# interface2.net
KiCad netlist of a schematic drawn in EAGLE
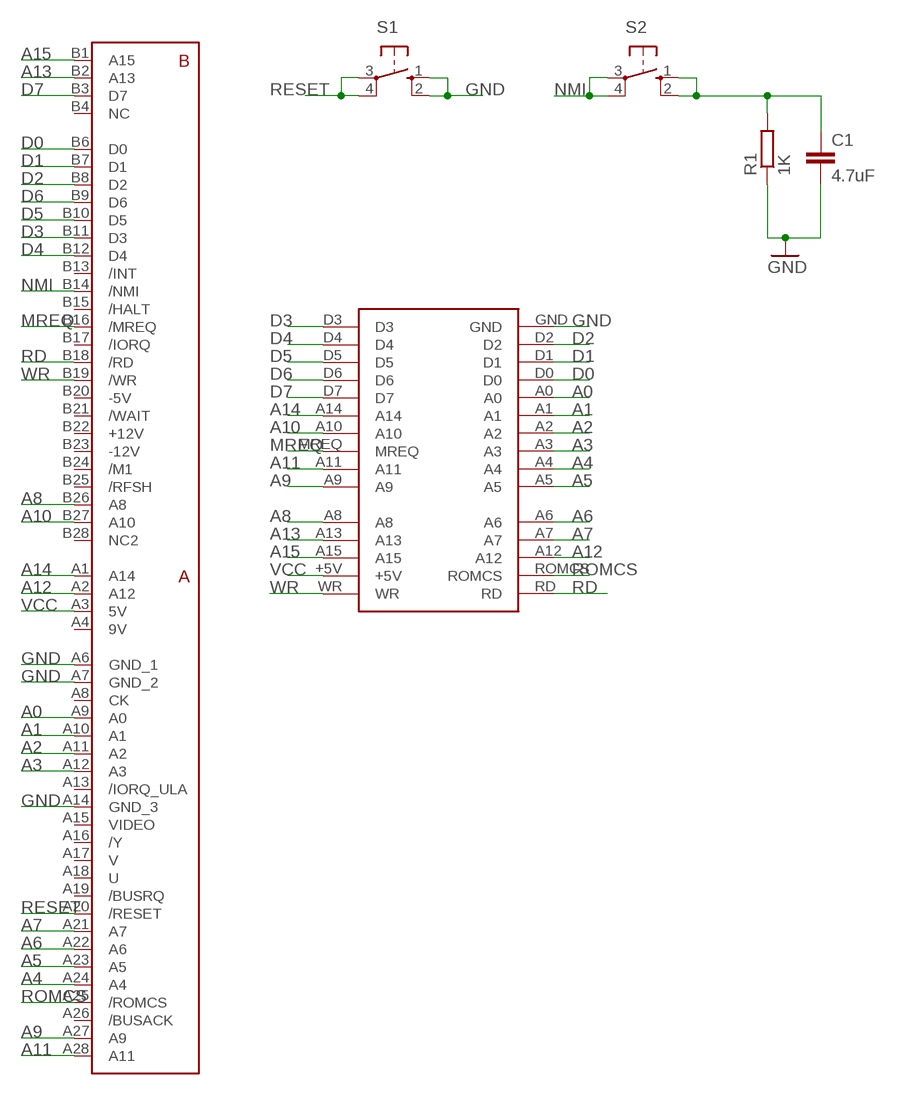
[diagram p0: schematic, sheet 1]

(export (version "E")
  (design (tool "Eeschema 10.0.6"))
  (components
    (comp (ref "C1")
      (value "4.7uF")
      (footprint "eagle-import:C025-025X050")
      (libsource (lib "eagle-import") (part "C-EU025-025X050"))
    )
    (comp (ref "R1")
      (value "1K")
      (footprint "eagle-import:0204_5")
      (libsource (lib "eagle-import") (part "R-EU_0204/5"))
    )
    (comp (ref "S1")
      (value "10-XX")
      (footprint "eagle-import:B3F-10XX")
      (fields (field (name "MPN") "B3F-1000"))
      (libsource (lib "eagle-import") (part "10-XX"))
    )
    (comp (ref "S2")
      (value "10-XX")
      (footprint "eagle-import:B3F-10XX")
      (fields (field (name "MPN") "B3F-1000"))
      (libsource (lib "eagle-import") (part "10-XX"))
    )
    (comp (ref "U$1")
      (value "ZX_CARTRIDGE")
      (footprint "eagle-import:ZX_CARTRIDGE")
      (libsource (lib "eagle-import") (part "ZX_CARTRIDGE"))
    )
    (comp (ref "U$3")
      (value "ZXSP_ED2X28_SPE")
      (footprint "eagle-import:2X28_SPE")
      (libsource (lib "eagle-import") (part "ZXSP_ED2X28_SPE"))
    )
  )
  (nets
    (net (code "1") (name "/+12V") (class "Default")
      (node (ref "U$3") (pin "B22") (pinfunction "+12V_B22") (pintype "power_in"))
    )
    (net (code "2") (name "/-5V") (class "Default")
      (node (ref "U$3") (pin "B20") (pinfunction "-5V_B20") (pintype "power_in"))
    )
    (net (code "3") (name "/-12V") (class "Default")
      (node (ref "U$3") (pin "B23") (pinfunction "-12V_B23") (pintype "power_in"))
    )
    (net (code "4") (name "/9V") (class "Default")
      (node (ref "U$3") (pin "A4") (pinfunction "9V_A4") (pintype "power_in"))
    )
    (net (code "5") (name "/A0") (class "Default")
      (node (ref "U$1") (pin "A0") (pinfunction "A0_A0") (pintype "bidirectional"))
      (node (ref "U$3") (pin "A9") (pinfunction "A0_A9") (pintype "bidirectional"))
    )
    (net (code "6") (name "/A1") (class "Default")
      (node (ref "U$1") (pin "A1") (pinfunction "A1_A1") (pintype "bidirectional"))
      (node (ref "U$3") (pin "A10") (pinfunction "A1_A10") (pintype "bidirectional"))
    )
    (net (code "7") (name "/A2") (class "Default")
      (node (ref "U$1") (pin "A2") (pinfunction "A2_A2") (pintype "bidirectional"))
      (node (ref "U$3") (pin "A11") (pinfunction "A2_A11") (pintype "bidirectional"))
    )
    (net (code "8") (name "/A3") (class "Default")
      (node (ref "U$1") (pin "A3") (pinfunction "A3_A3") (pintype "bidirectional"))
      (node (ref "U$3") (pin "A12") (pinfunction "A3_A12") (pintype "bidirectional"))
    )
    (net (code "9") (name "/A4") (class "Default")
      (node (ref "U$1") (pin "A4") (pinfunction "A4_A4") (pintype "bidirectional"))
      (node (ref "U$3") (pin "A24") (pinfunction "A4_A24") (pintype "bidirectional"))
    )
    (net (code "10") (name "/A5") (class "Default")
      (node (ref "U$1") (pin "A5") (pinfunction "A5_A5") (pintype "bidirectional"))
      (node (ref "U$3") (pin "A23") (pinfunction "A5_A23") (pintype "bidirectional"))
    )
    (net (code "11") (name "/A6") (class "Default")
      (node (ref "U$1") (pin "A6") (pinfunction "A6_A6") (pintype "bidirectional"))
      (node (ref "U$3") (pin "A22") (pinfunction "A6_A22") (pintype "bidirectional"))
    )
    (net (code "12") (name "/A7") (class "Default")
      (node (ref "U$1") (pin "A7") (pinfunction "A7_A7") (pintype "bidirectional"))
      (node (ref "U$3") (pin "A21") (pinfunction "A7_A21") (pintype "bidirectional"))
    )
    (net (code "13") (name "/A8") (class "Default")
      (node (ref "U$1") (pin "A8") (pinfunction "A8_A8") (pintype "bidirectional"))
      (node (ref "U$3") (pin "B26") (pinfunction "A8_B26") (pintype "bidirectional"))
    )
    (net (code "14") (name "/A9") (class "Default")
      (node (ref "U$1") (pin "A9") (pinfunction "A9_A9") (pintype "bidirectional"))
      (node (ref "U$3") (pin "A27") (pinfunction "A9_A27") (pintype "bidirectional"))
    )
    (net (code "15") (name "/A10") (class "Default")
      (node (ref "U$1") (pin "A10") (pinfunction "A10_A10") (pintype "bidirectional"))
      (node (ref "U$3") (pin "B27") (pinfunction "A10_B27") (pintype "bidirectional"))
    )
    (net (code "16") (name "/A11") (class "Default")
      (node (ref "U$1") (pin "A11") (pinfunction "A11_A11") (pintype "bidirectional"))
      (node (ref "U$3") (pin "A28") (pinfunction "A11_A28") (pintype "bidirectional"))
    )
    (net (code "17") (name "/A12") (class "Default")
      (node (ref "U$1") (pin "A12") (pinfunction "A12_A12") (pintype "bidirectional"))
      (node (ref "U$3") (pin "A2") (pinfunction "A12_A2") (pintype "bidirectional"))
    )
    (net (code "18") (name "/A13") (class "Default")
      (node (ref "U$1") (pin "A13") (pinfunction "A13_A13") (pintype "bidirectional"))
      (node (ref "U$3") (pin "B2") (pinfunction "A13_B2") (pintype "bidirectional"))
    )
    (net (code "19") (name "/A14") (class "Default")
      (node (ref "U$1") (pin "A14") (pinfunction "A14_A14") (pintype "bidirectional"))
      (node (ref "U$3") (pin "A1") (pinfunction "A14_A1") (pintype "bidirectional"))
    )
    (net (code "20") (name "/A15") (class "Default")
      (node (ref "U$1") (pin "A15") (pinfunction "A15_A15") (pintype "bidirectional"))
      (node (ref "U$3") (pin "B1") (pinfunction "A15_B1") (pintype "bidirectional"))
    )
    (net (code "21") (name "/D0") (class "Default")
      (node (ref "U$1") (pin "D0") (pinfunction "D0_D0") (pintype "bidirectional"))
      (node (ref "U$3") (pin "B6") (pinfunction "D0_B6") (pintype "bidirectional"))
    )
    (net (code "22") (name "/D1") (class "Default")
      (node (ref "U$1") (pin "D1") (pinfunction "D1_D1") (pintype "bidirectional"))
      (node (ref "U$3") (pin "B7") (pinfunction "D1_B7") (pintype "bidirectional"))
    )
    (net (code "23") (name "/D2") (class "Default")
      (node (ref "U$1") (pin "D2") (pinfunction "D2_D2") (pintype "bidirectional"))
      (node (ref "U$3") (pin "B8") (pinfunction "D2_B8") (pintype "bidirectional"))
    )
    (net (code "24") (name "/D3") (class "Default")
      (node (ref "U$1") (pin "D3") (pinfunction "D3_D3") (pintype "bidirectional"))
      (node (ref "U$3") (pin "B11") (pinfunction "D3_B11") (pintype "bidirectional"))
    )
    (net (code "25") (name "/D4") (class "Default")
      (node (ref "U$1") (pin "D4") (pinfunction "D4_D4") (pintype "bidirectional"))
      (node (ref "U$3") (pin "B12") (pinfunction "D4_B12") (pintype "bidirectional"))
    )
    (net (code "26") (name "/D5") (class "Default")
      (node (ref "U$1") (pin "D5") (pinfunction "D5_D5") (pintype "bidirectional"))
      (node (ref "U$3") (pin "B10") (pinfunction "D5_B10") (pintype "bidirectional"))
    )
    (net (code "27") (name "/D6") (class "Default")
      (node (ref "U$1") (pin "D6") (pinfunction "D6_D6") (pintype "bidirectional"))
      (node (ref "U$3") (pin "B9") (pinfunction "D6_B9") (pintype "bidirectional"))
    )
    (net (code "28") (name "/D7") (class "Default")
      (node (ref "U$1") (pin "D7") (pinfunction "D7_D7") (pintype "bidirectional"))
      (node (ref "U$3") (pin "B3") (pinfunction "D7_B3") (pintype "bidirectional"))
    )
    (net (code "29") (name "/MREQ") (class "Default")
      (node (ref "U$1") (pin "MREQ") (pinfunction "MREQ_MREQ") (pintype "bidirectional"))
      (node (ref "U$3") (pin "B16") (pinfunction "/MREQ_B16") (pintype "bidirectional"))
    )
    (net (code "30") (name "/NMI") (class "Default")
      (node (ref "S2") (pin "3") (pinfunction "P_3") (pintype "passive"))
      (node (ref "S2") (pin "4") (pinfunction "P1_4") (pintype "passive"))
      (node (ref "U$3") (pin "B14") (pinfunction "/NMI_B14") (pintype "bidirectional"))
    )
    (net (code "31") (name "/RD") (class "Default")
      (node (ref "U$1") (pin "RD") (pinfunction "RD_RD") (pintype "bidirectional"))
      (node (ref "U$3") (pin "B18") (pinfunction "/RD_B18") (pintype "bidirectional"))
    )
    (net (code "32") (name "/RESET") (class "Default")
      (node (ref "S1") (pin "3") (pinfunction "P_3") (pintype "passive"))
      (node (ref "S1") (pin "4") (pinfunction "P1_4") (pintype "passive"))
      (node (ref "U$3") (pin "A20") (pinfunction "/RESET_A20") (pintype "bidirectional"))
    )
    (net (code "33") (name "/ROMCS") (class "Default")
      (node (ref "U$1") (pin "ROMCS") (pinfunction "ROMCS_ROMCS") (pintype "bidirectional"))
      (node (ref "U$3") (pin "A25") (pinfunction "/ROMCS_A25") (pintype "bidirectional"))
    )
    (net (code "34") (name "/VCC") (class "Default")
      (node (ref "U$1") (pin "+5V") (pinfunction "+5V_+5V") (pintype "bidirectional"))
      (node (ref "U$3") (pin "A3") (pinfunction "5V_A3") (pintype "power_in"))
    )
    (net (code "35") (name "/WR") (class "Default")
      (node (ref "U$1") (pin "WR") (pinfunction "WR_WR") (pintype "bidirectional"))
      (node (ref "U$3") (pin "B19") (pinfunction "/WR_B19") (pintype "bidirectional"))
    )
    (net (code "36") (name "GND") (class "Default")
      (node (ref "C1") (pin "2") (pinfunction "2_2") (pintype "passive"))
      (node (ref "R1") (pin "1") (pinfunction "1_1") (pintype "passive"))
      (node (ref "S1") (pin "1") (pinfunction "S_1") (pintype "passive"))
      (node (ref "S1") (pin "2") (pinfunction "S1_2") (pintype "passive"))
      (node (ref "U$1") (pin "GND") (pinfunction "GND_GND") (pintype "bidirectional"))
      (node (ref "U$3") (pin "A14") (pinfunction "GND_3_A14") (pintype "power_in"))
      (node (ref "U$3") (pin "A6") (pinfunction "GND_1_A6") (pintype "power_in"))
      (node (ref "U$3") (pin "A7") (pinfunction "GND_2_A7") (pintype "power_in"))
    )
    (net (code "37") (name "Net-(S2-S)") (class "Default")
      (node (ref "C1") (pin "1") (pinfunction "1_1") (pintype "passive"))
      (node (ref "R1") (pin "2") (pinfunction "2_2") (pintype "passive"))
      (node (ref "S2") (pin "1") (pinfunction "S_1") (pintype "passive"))
      (node (ref "S2") (pin "2") (pinfunction "S1_2") (pintype "passive"))
    )
    (net (code "38") (name "unconnected-(U$3-CK-PadA8)") (class "Default")
      (node (ref "U$3") (pin "A8") (pinfunction "CK_A8") (pintype "bidirectional"))
    )
    (net (code "39") (name "unconnected-(U$3-NC-PadB4)") (class "Default")
      (node (ref "U$3") (pin "B4") (pinfunction "NC_B4") (pintype "no_connect"))
    )
    (net (code "40") (name "unconnected-(U$3-NC2-PadB28)") (class "Default")
      (node (ref "U$3") (pin "B28") (pinfunction "NC2_B28") (pintype "no_connect"))
    )
    (net (code "41") (name "unconnected-(U$3-U-PadA18)") (class "Default")
      (node (ref "U$3") (pin "A18") (pinfunction "U_A18") (pintype "bidirectional"))
    )
    (net (code "42") (name "unconnected-(U$3-V-PadA17)") (class "Default")
      (node (ref "U$3") (pin "A17") (pinfunction "V_A17") (pintype "bidirectional"))
    )
    (net (code "43") (name "unconnected-(U$3-VIDEO-PadA15)") (class "Default")
      (node (ref "U$3") (pin "A15") (pinfunction "VIDEO_A15") (pintype "bidirectional"))
    )
    (net (code "44") (name "unconnected-(U$3-{slash}BUSACK-PadA26)") (class "Default")
      (node (ref "U$3") (pin "A26") (pinfunction "/BUSACK_A26") (pintype "bidirectional"))
    )
    (net (code "45") (name "unconnected-(U$3-{slash}BUSRQ-PadA19)") (class "Default")
      (node (ref "U$3") (pin "A19") (pinfunction "/BUSRQ_A19") (pintype "bidirectional"))
    )
    (net (code "46") (name "unconnected-(U$3-{slash}HALT-PadB15)") (class "Default")
      (node (ref "U$3") (pin "B15") (pinfunction "/HALT_B15") (pintype "bidirectional"))
    )
    (net (code "47") (name "unconnected-(U$3-{slash}INT-PadB13)") (class "Default")
      (node (ref "U$3") (pin "B13") (pinfunction "/INT_B13") (pintype "bidirectional"))
    )
    (net (code "48") (name "unconnected-(U$3-{slash}IORQ-PadB17)") (class "Default")
      (node (ref "U$3") (pin "B17") (pinfunction "/IORQ_B17") (pintype "bidirectional"))
    )
    (net (code "49") (name "unconnected-(U$3-{slash}IORQ_ULA-PadA13)") (class "Default")
      (node (ref "U$3") (pin "A13") (pinfunction "/IORQ_ULA_A13") (pintype "bidirectional"))
    )
    (net (code "50") (name "unconnected-(U$3-{slash}M1-PadB24)") (class "Default")
      (node (ref "U$3") (pin "B24") (pinfunction "/M1_B24") (pintype "bidirectional"))
    )
    (net (code "51") (name "unconnected-(U$3-{slash}RFSH-PadB25)") (class "Default")
      (node (ref "U$3") (pin "B25") (pinfunction "/RFSH_B25") (pintype "bidirectional"))
    )
    (net (code "52") (name "unconnected-(U$3-{slash}WAIT-PadB21)") (class "Default")
      (node (ref "U$3") (pin "B21") (pinfunction "/WAIT_B21") (pintype "bidirectional"))
    )
    (net (code "53") (name "unconnected-(U$3-{slash}Y-PadA16)") (class "Default")
      (node (ref "U$3") (pin "A16") (pinfunction "/Y_A16") (pintype "bidirectional"))
    )
  )
)
